# McPiFace-MiniOled-V1.net
KiCad netlist of a schematic drawn in EAGLE
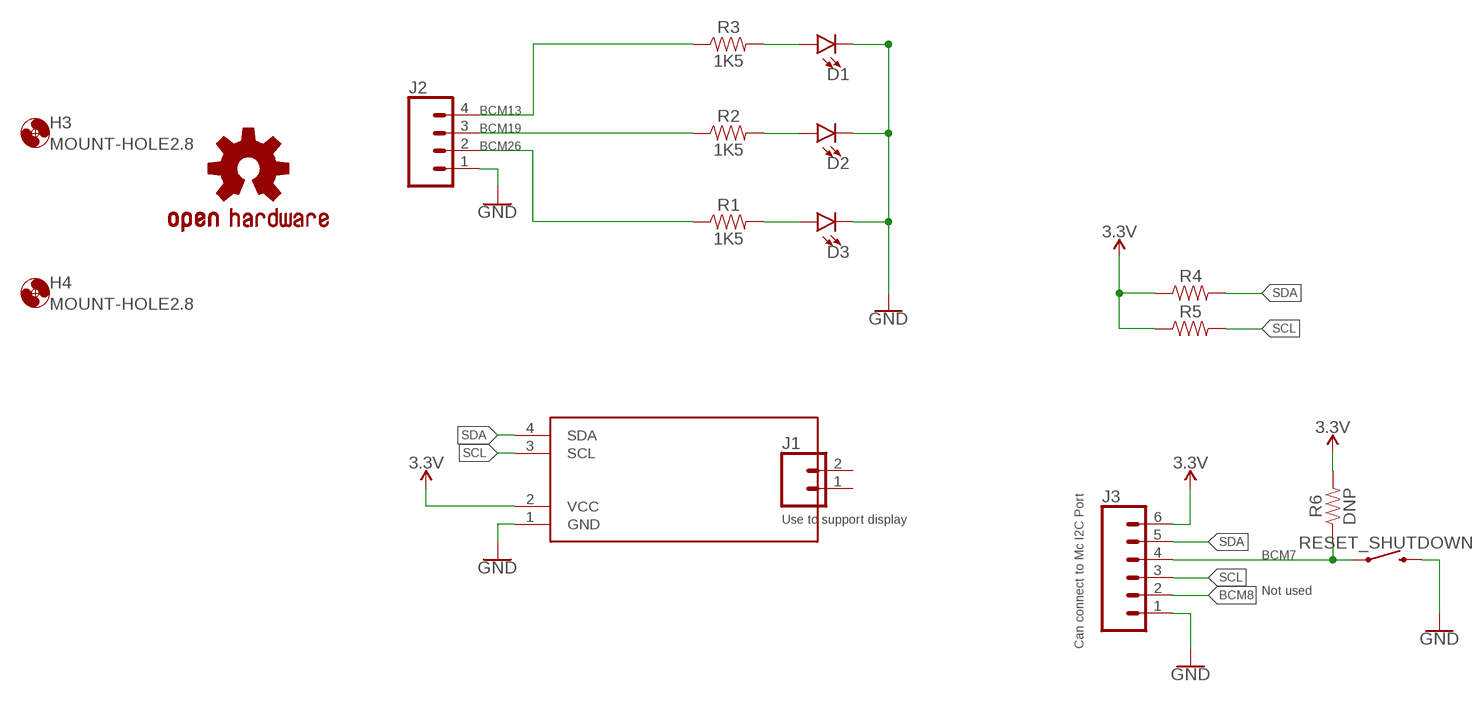
[diagram p0: schematic, sheet 1]

(export (version "E")
  (design (tool "Eeschema 10.0.6"))
  (components
    (comp (ref "D1")
      (value "LED1206-BOTTOM-1.6MM")
      (footprint "eagle-import:LED-1206-BOTTOM-1.6MM")
      (libsource (lib "eagle-import") (part "LED1206-BOTTOM-1.6MM"))
    )
    (comp (ref "D2")
      (value "LED1206-BOTTOM-1.6MM")
      (footprint "eagle-import:LED-1206-BOTTOM-1.6MM")
      (libsource (lib "eagle-import") (part "LED1206-BOTTOM-1.6MM"))
    )
    (comp (ref "D3")
      (value "LED1206-BOTTOM-1.6MM")
      (footprint "eagle-import:LED-1206-BOTTOM-1.6MM")
      (libsource (lib "eagle-import") (part "LED1206-BOTTOM-1.6MM"))
    )
    (comp (ref "DISPLAY")
      (value "DISPLAY0.91_INCH_DISPLAY")
      (footprint "eagle-import:I2C_DISPLAY_0.91_INCH")
      (libsource (lib "eagle-import") (part "DISPLAY0.91_INCH_DISPLAY"))
    )
    (comp (ref "H3")
      (value "MOUNT-HOLE2.8")
      (footprint "eagle-import:2,8")
      (libsource (lib "eagle-import") (part "MOUNT-HOLE2.8"))
    )
    (comp (ref "H4")
      (value "MOUNT-HOLE2.8")
      (footprint "eagle-import:2,8")
      (libsource (lib "eagle-import") (part "MOUNT-HOLE2.8"))
    )
    (comp (ref "J1")
      (value "CONN_021X02_NO_SILK")
      (footprint "eagle-import:1X02_NO_SILK")
      (libsource (lib "eagle-import") (part "CONN_021X02_NO_SILK"))
    )
    (comp (ref "J2")
      (value "CONN_04SMD2")
      (footprint "eagle-import:1X04_1MM_RA")
      (libsource (lib "eagle-import") (part "CONN_04SMD2"))
    )
    (comp (ref "J3")
      (value "CONN_06SMD-1MM")
      (footprint "eagle-import:1X06-1MM")
      (libsource (lib "eagle-import") (part "CONN_06SMD-1MM"))
    )
    (comp (ref "LOGO1")
      (value "OSHW-LOGOL")
      (footprint "eagle-import:OSHW-LOGO-L")
      (libsource (lib "eagle-import") (part "OSHW-LOGOL"))
    )
    (comp (ref "R1")
      (value "1K5")
      (footprint "eagle-import:0805")
      (libsource (lib "eagle-import") (part "RESISTOR0805"))
    )
    (comp (ref "R2")
      (value "1K5")
      (footprint "eagle-import:0805")
      (libsource (lib "eagle-import") (part "RESISTOR0805"))
    )
    (comp (ref "R3")
      (value "1K5")
      (footprint "eagle-import:0805")
      (libsource (lib "eagle-import") (part "RESISTOR0805"))
    )
    (comp (ref "R4")
      (value "RESISTOR0805")
      (footprint "eagle-import:0805")
      (libsource (lib "eagle-import") (part "RESISTOR0805"))
    )
    (comp (ref "R5")
      (value "RESISTOR0805")
      (footprint "eagle-import:0805")
      (libsource (lib "eagle-import") (part "RESISTOR0805"))
    )
    (comp (ref "R6")
      (value "DNP")
      (footprint "eagle-import:0805")
      (libsource (lib "eagle-import") (part "RESISTOR0805"))
    )
    (comp (ref "RESET_SHUTDOWN")
      (value "Reset/Powerdown")
      (footprint "eagle-import:TACTILE_SWITCH_PTH_6.0MM_NO_TOP_RESIST")
      (libsource (lib "eagle-import") (part "MOMENTARY-SWITCH-SPSTTACKTILE_SWITCH_PTH_6.0MM_NO_TOP_RESIST"))
    )
  )
  (nets
    (net (code "1") (name "/BCM7") (class "Default")
      (node (ref "J3") (pin "4") (pinfunction "4_4") (pintype "passive"))
      (node (ref "R6") (pin "1") (pinfunction "1_1") (pintype "passive"))
      (node (ref "RESET_SHUTDOWN") (pin "1") (pinfunction "1_1") (pintype "passive"))
    )
    (net (code "2") (name "/BCM13") (class "Default")
      (node (ref "J2") (pin "4") (pinfunction "4_4") (pintype "passive"))
      (node (ref "R3") (pin "1") (pinfunction "1_1") (pintype "passive"))
    )
    (net (code "3") (name "/BCM19") (class "Default")
      (node (ref "J2") (pin "3") (pinfunction "3_3") (pintype "passive"))
      (node (ref "R2") (pin "1") (pinfunction "1_1") (pintype "passive"))
    )
    (net (code "4") (name "/BCM26") (class "Default")
      (node (ref "J2") (pin "2") (pinfunction "2_2") (pintype "passive"))
      (node (ref "R1") (pin "1") (pinfunction "1_1") (pintype "passive"))
    )
    (net (code "5") (name "3.3V") (class "Default")
      (node (ref "DISPLAY") (pin "2") (pinfunction "VCC_2") (pintype "power_in"))
      (node (ref "J3") (pin "6") (pinfunction "6_6") (pintype "passive"))
      (node (ref "R4") (pin "1") (pinfunction "1_1") (pintype "passive"))
      (node (ref "R5") (pin "1") (pinfunction "1_1") (pintype "passive"))
      (node (ref "R6") (pin "2") (pinfunction "2_2") (pintype "passive"))
    )
    (net (code "6") (name "BCM8") (class "Default")
      (node (ref "J3") (pin "2") (pinfunction "2_2") (pintype "passive"))
    )
    (net (code "7") (name "GND") (class "Default")
      (node (ref "D1") (pin "C") (pinfunction "C_C") (pintype "passive"))
      (node (ref "D2") (pin "C") (pinfunction "C_C") (pintype "passive"))
      (node (ref "D3") (pin "C") (pinfunction "C_C") (pintype "passive"))
      (node (ref "DISPLAY") (pin "1") (pinfunction "GND_1") (pintype "power_in"))
      (node (ref "J2") (pin "1") (pinfunction "1_1") (pintype "passive"))
      (node (ref "J3") (pin "1") (pinfunction "1_1") (pintype "passive"))
      (node (ref "RESET_SHUTDOWN") (pin "3") (pinfunction "2_3") (pintype "passive"))
    )
    (net (code "8") (name "Net-(D1-PadA)") (class "Default")
      (node (ref "D1") (pin "A") (pinfunction "A_A") (pintype "passive"))
      (node (ref "R3") (pin "2") (pinfunction "2_2") (pintype "passive"))
    )
    (net (code "9") (name "Net-(D2-PadA)") (class "Default")
      (node (ref "D2") (pin "A") (pinfunction "A_A") (pintype "passive"))
      (node (ref "R2") (pin "2") (pinfunction "2_2") (pintype "passive"))
    )
    (net (code "10") (name "Net-(D3-PadA)") (class "Default")
      (node (ref "D3") (pin "A") (pinfunction "A_A") (pintype "passive"))
      (node (ref "R1") (pin "2") (pinfunction "2_2") (pintype "passive"))
    )
    (net (code "11") (name "SCL") (class "Default")
      (node (ref "DISPLAY") (pin "3") (pinfunction "SCL_3") (pintype "bidirectional"))
      (node (ref "J3") (pin "3") (pinfunction "3_3") (pintype "passive"))
      (node (ref "R5") (pin "2") (pinfunction "2_2") (pintype "passive"))
    )
    (net (code "12") (name "SDA") (class "Default")
      (node (ref "DISPLAY") (pin "4") (pinfunction "SDA_4") (pintype "bidirectional"))
      (node (ref "J3") (pin "5") (pinfunction "5_5") (pintype "passive"))
      (node (ref "R4") (pin "2") (pinfunction "2_2") (pintype "passive"))
    )
    (net (code "13") (name "unconnected-(J1-Pad1)") (class "Default")
      (node (ref "J1") (pin "1") (pinfunction "1_1") (pintype "passive"))
    )
    (net (code "14") (name "unconnected-(J1-Pad2)") (class "Default")
      (node (ref "J1") (pin "2") (pinfunction "2_2") (pintype "passive"))
    )
  )
)
